# proiect_schematic_v19.net
KiCad netlist of a schematic drawn in EAGLE
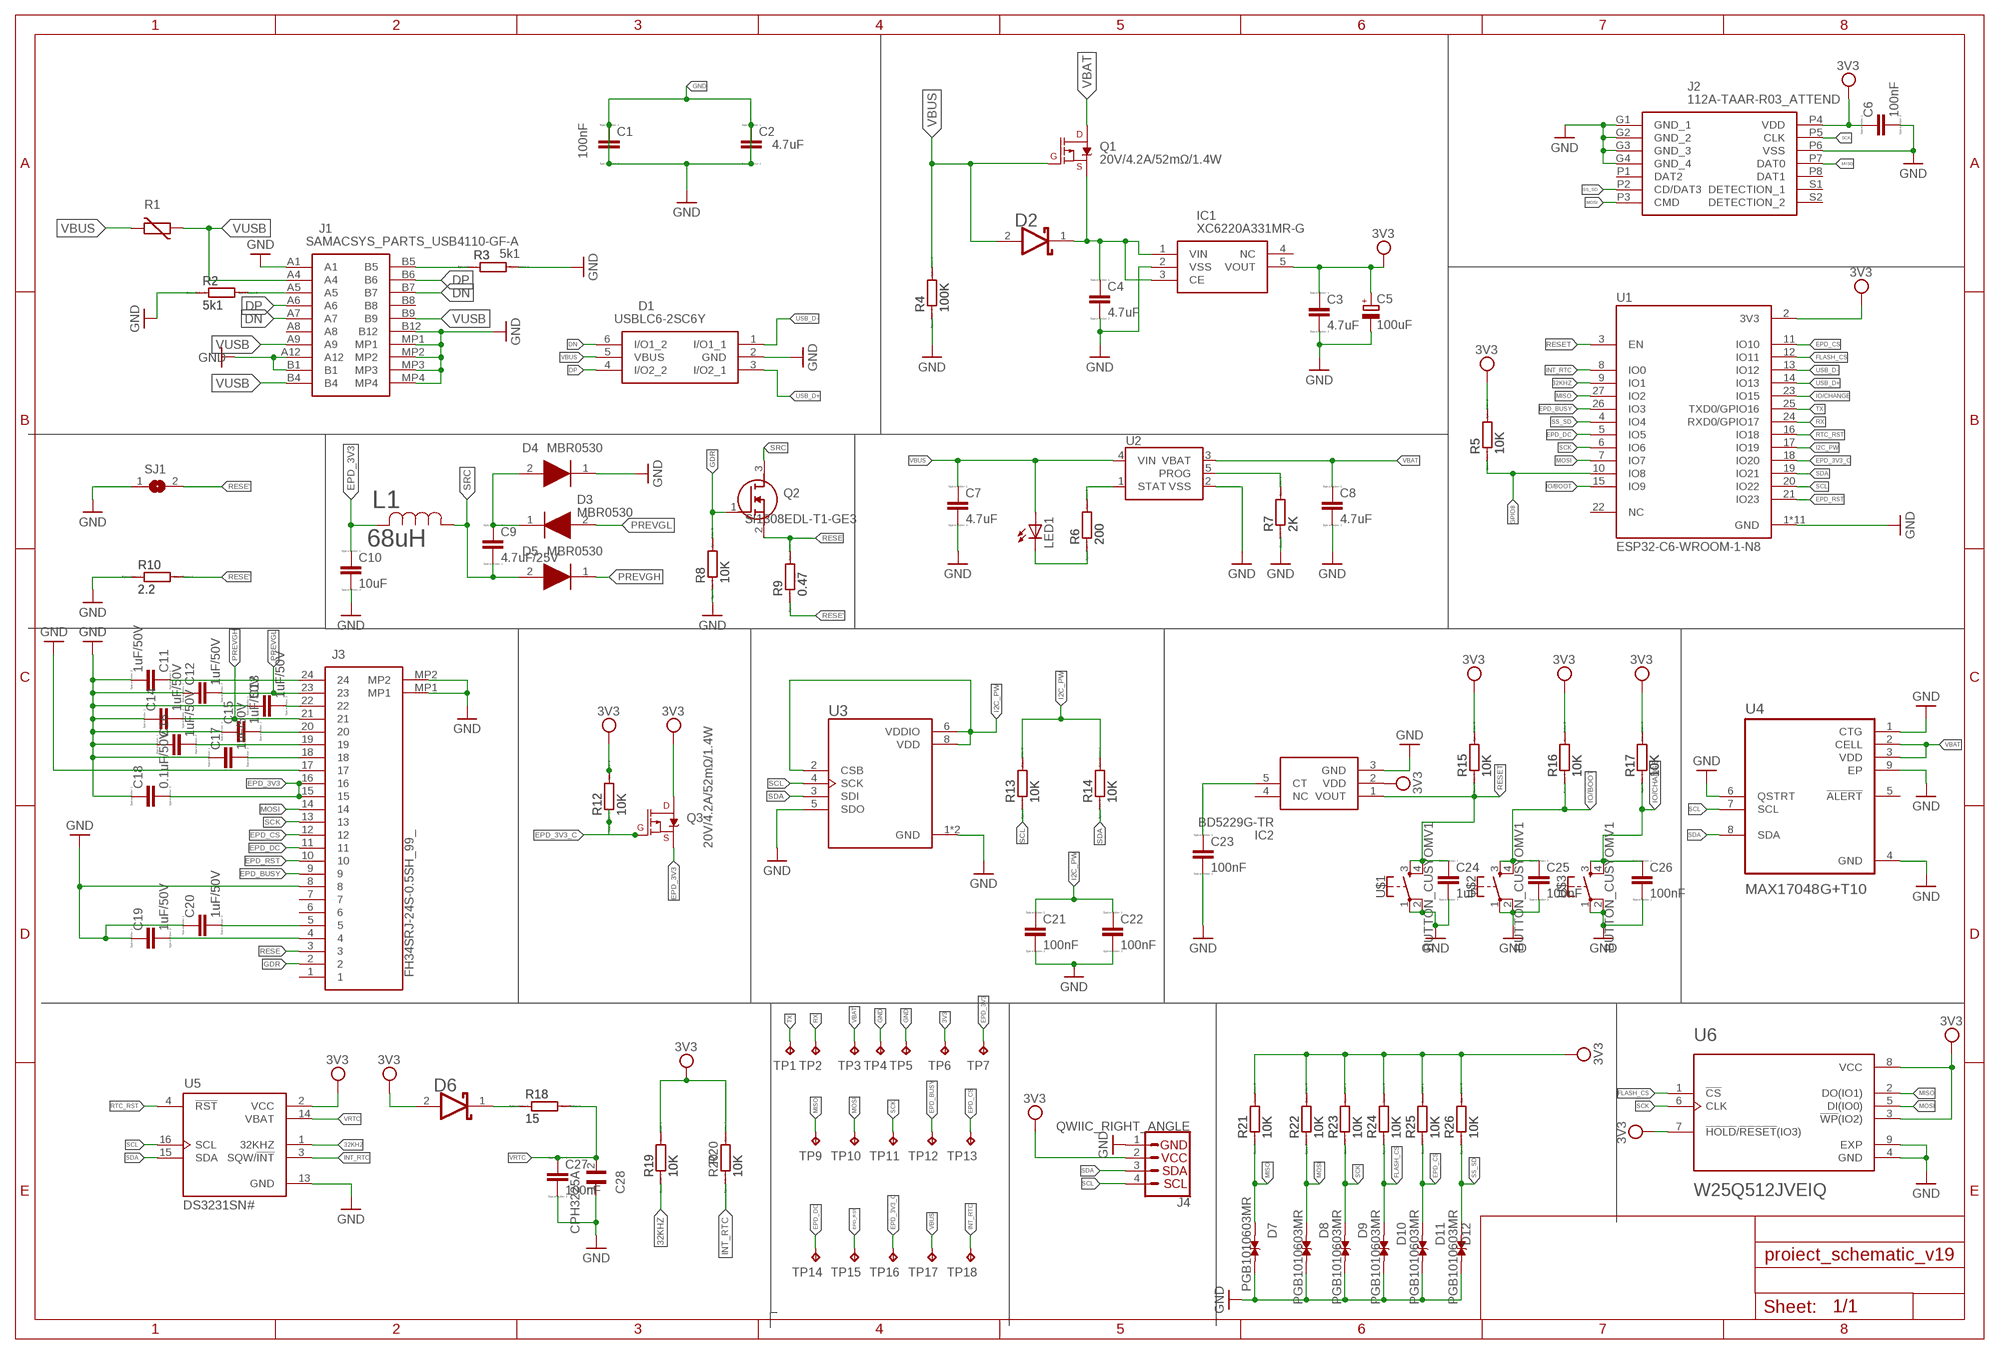
[diagram p0: schematic, sheet 1]

(export (version "E")
  (design (tool "Eeschema 10.0.6"))
  (components
    (comp (ref "C1")
      (value "100nF")
      (footprint "eagle-import:ESP32_WROVER_EAGLE-LTSPICE_C0402")
      (libsource (lib "eagle-import") (part "ESP32_WROVER_EAGLE-LTSPICE_CC0402"))
    )
    (comp (ref "C2")
      (value "4.7uF")
      (footprint "eagle-import:ESP32_WROVER_EAGLE-LTSPICE_C0402")
      (libsource (lib "eagle-import") (part "ESP32_WROVER_EAGLE-LTSPICE_CC0402"))
    )
    (comp (ref "C3")
      (value "4.7uF")
      (footprint "eagle-import:EAGLE-LTSPICE_C0402")
      (libsource (lib "eagle-import") (part "EAGLE-LTSPICE_CC0402"))
    )
    (comp (ref "C4")
      (value "4.7uF")
      (footprint "eagle-import:EAGLE-LTSPICE_C0402")
      (libsource (lib "eagle-import") (part "EAGLE-LTSPICE_CC0402"))
    )
    (comp (ref "C5")
      (value "100uF")
      (footprint "eagle-import:RCL_CT3528")
      (libsource (lib "eagle-import") (part "RCL_CPOL-EUCT3528"))
    )
    (comp (ref "C6")
      (value "100nF")
      (footprint "eagle-import:ESP32_WROVER_EAGLE-LTSPICE_C0402")
      (libsource (lib "eagle-import") (part "ESP32_WROVER_EAGLE-LTSPICE_CC0402"))
    )
    (comp (ref "C7")
      (value "4.7uF")
      (footprint "eagle-import:ESP32_WROVER_EAGLE-LTSPICE_C0402")
      (libsource (lib "eagle-import") (part "ESP32_WROVER_EAGLE-LTSPICE_CC0402"))
    )
    (comp (ref "C8")
      (value "4.7uF")
      (footprint "eagle-import:ESP32_WROVER_EAGLE-LTSPICE_C0402")
      (libsource (lib "eagle-import") (part "ESP32_WROVER_EAGLE-LTSPICE_CC0402"))
    )
    (comp (ref "C9")
      (value "4.7uF/25V")
      (footprint "eagle-import:ESP32_WROVER_EAGLE-LTSPICE_C0402")
      (libsource (lib "eagle-import") (part "ESP32_WROVER_EAGLE-LTSPICE_CC0402"))
    )
    (comp (ref "C10")
      (value "10uF")
      (footprint "eagle-import:ESP32_WROVER_EAGLE-LTSPICE_C0402")
      (libsource (lib "eagle-import") (part "ESP32_WROVER_EAGLE-LTSPICE_CC0402"))
    )
    (comp (ref "C11")
      (value "1uF/50V")
      (footprint "eagle-import:ESP32_WROVER_EAGLE-LTSPICE_C0402")
      (libsource (lib "eagle-import") (part "ESP32_WROVER_EAGLE-LTSPICE_CC0402"))
    )
    (comp (ref "C12")
      (value "1uF/50V")
      (footprint "eagle-import:ESP32_WROVER_EAGLE-LTSPICE_C0402")
      (libsource (lib "eagle-import") (part "ESP32_WROVER_EAGLE-LTSPICE_CC0402"))
    )
    (comp (ref "C13")
      (value "1uF/50V")
      (footprint "eagle-import:ESP32_WROVER_EAGLE-LTSPICE_C0402")
      (libsource (lib "eagle-import") (part "ESP32_WROVER_EAGLE-LTSPICE_CC0402"))
    )
    (comp (ref "C14")
      (value "1uF/50V")
      (footprint "eagle-import:ESP32_WROVER_EAGLE-LTSPICE_C0402")
      (libsource (lib "eagle-import") (part "ESP32_WROVER_EAGLE-LTSPICE_CC0402"))
    )
    (comp (ref "C15")
      (value "1uF/50V")
      (footprint "eagle-import:ESP32_WROVER_EAGLE-LTSPICE_C0402")
      (libsource (lib "eagle-import") (part "ESP32_WROVER_EAGLE-LTSPICE_CC0402"))
    )
    (comp (ref "C16")
      (value "1uF/50V")
      (footprint "eagle-import:ESP32_WROVER_EAGLE-LTSPICE_C0402")
      (libsource (lib "eagle-import") (part "ESP32_WROVER_EAGLE-LTSPICE_CC0402"))
    )
    (comp (ref "C17")
      (value "1uF/50V")
      (footprint "eagle-import:ESP32_WROVER_EAGLE-LTSPICE_C0402")
      (libsource (lib "eagle-import") (part "ESP32_WROVER_EAGLE-LTSPICE_CC0402"))
    )
    (comp (ref "C18")
      (value "0.1uF/50V")
      (footprint "eagle-import:ESP32_WROVER_EAGLE-LTSPICE_C0402")
      (libsource (lib "eagle-import") (part "ESP32_WROVER_EAGLE-LTSPICE_CC0402"))
    )
    (comp (ref "C19")
      (value "1uF/50V")
      (footprint "eagle-import:ESP32_WROVER_EAGLE-LTSPICE_C0402")
      (libsource (lib "eagle-import") (part "ESP32_WROVER_EAGLE-LTSPICE_CC0402"))
    )
    (comp (ref "C20")
      (value "1uF/50V")
      (footprint "eagle-import:ESP32_WROVER_EAGLE-LTSPICE_C0402")
      (libsource (lib "eagle-import") (part "ESP32_WROVER_EAGLE-LTSPICE_CC0402"))
    )
    (comp (ref "C21")
      (value "100nF")
      (footprint "eagle-import:ESP32_WROVER_EAGLE-LTSPICE_C0402")
      (libsource (lib "eagle-import") (part "ESP32_WROVER_EAGLE-LTSPICE_CC0402"))
    )
    (comp (ref "C22")
      (value "100nF")
      (footprint "eagle-import:ESP32_WROVER_EAGLE-LTSPICE_C0402")
      (libsource (lib "eagle-import") (part "ESP32_WROVER_EAGLE-LTSPICE_CC0402"))
    )
    (comp (ref "C23")
      (value "100nF")
      (footprint "eagle-import:ESP32_WROVER_EAGLE-LTSPICE_C0402")
      (libsource (lib "eagle-import") (part "ESP32_WROVER_EAGLE-LTSPICE_CC0402"))
    )
    (comp (ref "C24")
      (value "1uF")
      (footprint "eagle-import:ESP32_WROVER_EAGLE-LTSPICE_C0402")
      (libsource (lib "eagle-import") (part "ESP32_WROVER_EAGLE-LTSPICE_CC0402"))
    )
    (comp (ref "C25")
      (value "100nF")
      (footprint "eagle-import:ESP32_WROVER_EAGLE-LTSPICE_C0402")
      (libsource (lib "eagle-import") (part "ESP32_WROVER_EAGLE-LTSPICE_CC0402"))
    )
    (comp (ref "C26")
      (value "100nF")
      (footprint "eagle-import:ESP32_WROVER_EAGLE-LTSPICE_C0402")
      (libsource (lib "eagle-import") (part "ESP32_WROVER_EAGLE-LTSPICE_CC0402"))
    )
    (comp (ref "C27")
      (value "100nF")
      (footprint "eagle-import:ESP32_WROVER_EAGLE-LTSPICE_C0402")
      (libsource (lib "eagle-import") (part "ESP32_WROVER_EAGLE-LTSPICE_CC0402"))
    )
    (comp (ref "C28")
      (value "CPH3225A")
      (footprint "eagle-import:CAPCP3225X100N")
      (fields (field (name "MF") "Seiko Instruments"))
      (libsource (lib "eagle-import") (part "CPH3225A"))
    )
    (comp (ref "D1")
      (value "USBLC6-2SC6Y")
      (footprint "eagle-import:SOT95P280X145-6N")
      (fields (field (name "MF") "STMicroelectronics"))
      (libsource (lib "eagle-import") (part "USBLC6-2SC6Y"))
    )
    (comp (ref "D2")
      (value "ESP32_WROVER_AVX---SD0805S020S1R0_AVX_SD0805S020S1R0_0_0AVX_SD0805S020S1R0_0_0")
      (footprint "eagle-import:ESP32_WROVER_AVX---SD0805S020S1R0_AVX_SD0805S020S1R0_0")
      (fields
        (field (name "DIGIKEY_PART_NUMBER") "478-7800-1-ND")
        (field (name "MF") "AVX")
        (field (name "MOUSER_PART_NUMBER") "581-SD0805S020S1R0")
      )
      (libsource (lib "eagle-import") (part "ESP32_WROVER_AVX---SD0805S020S1R0_AVX_SD0805S020S1R0_0_0AVX_SD0805S020S1R0_0_0"))
    )
    (comp (ref "D3")
      (value "MBR0530")
      (footprint "eagle-import:SOD3716X135N")
      (fields (field (name "MF") "ON Semiconductor"))
      (libsource (lib "eagle-import") (part "MBR0530"))
    )
    (comp (ref "D4")
      (value "MBR0530")
      (footprint "eagle-import:SOD3716X135N")
      (fields (field (name "MF") "ON Semiconductor"))
      (libsource (lib "eagle-import") (part "MBR0530"))
    )
    (comp (ref "D5")
      (value "MBR0530")
      (footprint "eagle-import:SOD3716X135N")
      (fields (field (name "MF") "ON Semiconductor"))
      (libsource (lib "eagle-import") (part "MBR0530"))
    )
    (comp (ref "D6")
      (value "ESP32_WROVER_AVX---SD0805S020S1R0_AVX_SD0805S020S1R0_0_0AVX_SD0805S020S1R0_0_0")
      (footprint "eagle-import:ESP32_WROVER_AVX---SD0805S020S1R0_AVX_SD0805S020S1R0_0")
      (fields
        (field (name "DIGIKEY_PART_NUMBER") "478-7800-1-ND")
        (field (name "MF") "AVX")
        (field (name "MOUSER_PART_NUMBER") "581-SD0805S020S1R0")
      )
      (libsource (lib "eagle-import") (part "ESP32_WROVER_AVX---SD0805S020S1R0_AVX_SD0805S020S1R0_0_0AVX_SD0805S020S1R0_0_0"))
    )
    (comp (ref "D7")
      (value "PGB1010603MR")
      (footprint "eagle-import:DIOC1608X36N")
      (fields (field (name "MF") "Littelfuse Inc."))
      (libsource (lib "eagle-import") (part "PGB1010603MR"))
    )
    (comp (ref "D8")
      (value "PGB1010603MR")
      (footprint "eagle-import:DIOC1608X36N")
      (fields (field (name "MF") "Littelfuse Inc."))
      (libsource (lib "eagle-import") (part "PGB1010603MR"))
    )
    (comp (ref "D9")
      (value "PGB1010603MR")
      (footprint "eagle-import:DIOC1608X36N")
      (fields (field (name "MF") "Littelfuse Inc."))
      (libsource (lib "eagle-import") (part "PGB1010603MR"))
    )
    (comp (ref "D10")
      (value "PGB1010603MR")
      (footprint "eagle-import:DIOC1608X36N")
      (fields (field (name "MF") "Littelfuse Inc."))
      (libsource (lib "eagle-import") (part "PGB1010603MR"))
    )
    (comp (ref "D11")
      (value "PGB1010603MR")
      (footprint "eagle-import:DIOC1608X36N")
      (fields (field (name "MF") "Littelfuse Inc."))
      (libsource (lib "eagle-import") (part "PGB1010603MR"))
    )
    (comp (ref "D12")
      (value "PGB1010603MR")
      (footprint "eagle-import:DIOC1608X36N")
      (fields (field (name "MF") "Littelfuse Inc."))
      (libsource (lib "eagle-import") (part "PGB1010603MR"))
    )
    (comp (ref "IC1")
      (value "XC6220A331MR-G")
      (footprint "eagle-import:SOT95P280X120-5N")
      (fields (field (name "MOUSER_PART_NUMBER") "865-XC6220A331MR-G"))
      (libsource (lib "eagle-import") (part "XC6220A331MR-G"))
    )
    (comp (ref "IC2")
      (value "BD5229G-TR")
      (footprint "eagle-import:SOT95P280X125-5N")
      (fields (field (name "MOUSER_PART_NUMBER") "755-BD5229G-TR"))
      (libsource (lib "eagle-import") (part "BD5229G-TR"))
    )
    (comp (ref "J1")
      (value "SAMACSYS_PARTS_USB4110-GF-A")
      (footprint "eagle-import:SAMACSYS_PARTS_USB4110GFA")
      (fields
        (field (name "MANUFACTURER_PART_NUMBER") "USB4110-GF-A")
        (field (name "MOUSER_PART_NUMBER") "640-USB4110-GF-A")
      )
      (libsource (lib "eagle-import") (part "SAMACSYS_PARTS_USB4110-GF-A"))
    )
    (comp (ref "J2")
      (value "112A-TAAR-R03_ATTEND")
      (footprint "eagle-import:112ATAARR03ATTEND")
      (fields (field (name "MANUFACTURER_PART_NUMBER") "112A-TAAR-R03 ATTEND"))
      (libsource (lib "eagle-import") (part "112A-TAAR-R03_ATTEND"))
    )
    (comp (ref "J3")
      (value "FH34SRJ-24S-0.5SH_99_")
      (footprint "eagle-import:FH34SRJ24S05SH99")
      (fields
        (field (name "MANUFACTURER_PART_NUMBER") "FH34SRJ-24S-0.5SH(99)")
        (field (name "MOUSER_PART_NUMBER") "798-FH34SRJ24S05SH99")
      )
      (libsource (lib "eagle-import") (part "FH34SRJ-24S-0.5SH_99_"))
    )
    (comp (ref "J4")
      (value "QWIIC_RIGHT_ANGLE")
      (footprint "eagle-import:JST04_1MM_RA")
      (libsource (lib "eagle-import") (part "QWIIC_CONNECTORJS-1MM"))
    )
    (comp (ref "L1")
      (value "68uH")
      (footprint "eagle-import:IND_4828-WE-TPC_WRE")
      (fields
        (field (name "MANUFACTURER_PART_NUMBER") "744043680")
        (field (name "COPYRIGHT") "Copyright (C) 2024 Ultra Librarian. All rights reserved.")
      )
      (libsource (lib "eagle-import") (part "744043680IND_4828-WE-TPC_WRE"))
    )
    (comp (ref "LED1")
      (value "ADAFRUIT_LEDCHIP-LED0603")
      (footprint "eagle-import:ADAFRUIT_CHIP-LED0603")
      (libsource (lib "eagle-import") (part "ADAFRUIT_LEDCHIP-LED0603"))
    )
    (comp (ref "Q1")
      (value "20V/4.2A/52mΩ/1.4W")
      (footprint "eagle-import:ESP32_WROVER_SPARKFUN-DISCRETESEMI_SOT23-3")
      (libsource (lib "eagle-import") (part "ESP32_WROVER_SPARKFUN-DISCRETESEMI_MOSFET_PCH-DMG2305UX-7"))
    )
    (comp (ref "Q2")
      (value "SI1308EDL-T1-GE3")
      (footprint "eagle-import:SOT65P210X110-3N")
      (fields (field (name "MF") "Vishay Siliconix"))
      (libsource (lib "eagle-import") (part "SI1308EDL-T1-GE3"))
    )
    (comp (ref "Q3")
      (value "20V/4.2A/52mΩ/1.4W")
      (footprint "eagle-import:ESP32_WROVER_SPARKFUN-DISCRETESEMI_SOT23-3")
      (libsource (lib "eagle-import") (part "ESP32_WROVER_SPARKFUN-DISCRETESEMI_MOSFET_PCH-DMG2305UX-7"))
    )
    (comp (ref "R1")
      (value "ESP32C6_VARISTORCN1812")
      (footprint "eagle-import:ESP32C6_VARISTOR_CT_CN1812")
      (libsource (lib "eagle-import") (part "ESP32C6_VARISTORCN1812"))
    )
    (comp (ref "R2")
      (value "5k1")
      (footprint "eagle-import:ESP32_WROVER_EAGLE-LTSPICE_R0402")
      (libsource (lib "eagle-import") (part "ESP32_WROVER_EAGLE-LTSPICE_RR0402"))
    )
    (comp (ref "R3")
      (value "5k1")
      (footprint "eagle-import:ESP32_WROVER_EAGLE-LTSPICE_R0402")
      (libsource (lib "eagle-import") (part "ESP32_WROVER_EAGLE-LTSPICE_RR0402"))
    )
    (comp (ref "R4")
      (value "100K")
      (footprint "eagle-import:ESP32_WROVER_EAGLE-LTSPICE_R0402")
      (libsource (lib "eagle-import") (part "ESP32_WROVER_EAGLE-LTSPICE_RR0402"))
    )
    (comp (ref "R5")
      (value "10K")
      (footprint "eagle-import:ESP32_WROVER_EAGLE-LTSPICE_R0402")
      (libsource (lib "eagle-import") (part "ESP32_WROVER_EAGLE-LTSPICE_RR0402"))
    )
    (comp (ref "R6")
      (value "200")
      (footprint "eagle-import:ESP32_WROVER_EAGLE-LTSPICE_R0402")
      (libsource (lib "eagle-import") (part "ESP32_WROVER_EAGLE-LTSPICE_RR0402"))
    )
    (comp (ref "R7")
      (value "2K")
      (footprint "eagle-import:ESP32_WROVER_EAGLE-LTSPICE_R0402")
      (libsource (lib "eagle-import") (part "ESP32_WROVER_EAGLE-LTSPICE_RR0402"))
    )
    (comp (ref "R8")
      (value "10K")
      (footprint "eagle-import:ESP32_WROVER_EAGLE-LTSPICE_R0402")
      (libsource (lib "eagle-import") (part "ESP32_WROVER_EAGLE-LTSPICE_RR0402"))
    )
    (comp (ref "R9")
      (value "0.47")
      (footprint "eagle-import:ESP32_WROVER_EAGLE-LTSPICE_R0402")
      (libsource (lib "eagle-import") (part "ESP32_WROVER_EAGLE-LTSPICE_RR0402"))
    )
    (comp (ref "R10")
      (value "2.2")
      (footprint "eagle-import:ESP32_WROVER_EAGLE-LTSPICE_R0402")
      (libsource (lib "eagle-import") (part "ESP32_WROVER_EAGLE-LTSPICE_RR0402"))
    )
    (comp (ref "R12")
      (value "10K")
      (footprint "eagle-import:ESP32_WROVER_EAGLE-LTSPICE_R0402")
      (libsource (lib "eagle-import") (part "ESP32_WROVER_EAGLE-LTSPICE_RR0402"))
    )
    (comp (ref "R13")
      (value "10K")
      (footprint "eagle-import:ESP32_WROVER_EAGLE-LTSPICE_R0402")
      (libsource (lib "eagle-import") (part "ESP32_WROVER_EAGLE-LTSPICE_RR0402"))
    )
    (comp (ref "R14")
      (value "10K")
      (footprint "eagle-import:ESP32_WROVER_EAGLE-LTSPICE_R0402")
      (libsource (lib "eagle-import") (part "ESP32_WROVER_EAGLE-LTSPICE_RR0402"))
    )
    (comp (ref "R15")
      (value "10K")
      (footprint "eagle-import:ESP32_WROVER_EAGLE-LTSPICE_R0402")
      (libsource (lib "eagle-import") (part "ESP32_WROVER_EAGLE-LTSPICE_RR0402"))
    )
    (comp (ref "R16")
      (value "10K")
      (footprint "eagle-import:ESP32_WROVER_EAGLE-LTSPICE_R0402")
      (libsource (lib "eagle-import") (part "ESP32_WROVER_EAGLE-LTSPICE_RR0402"))
    )
    (comp (ref "R17")
      (value "10K")
      (footprint "eagle-import:ESP32_WROVER_EAGLE-LTSPICE_R0402")
      (libsource (lib "eagle-import") (part "ESP32_WROVER_EAGLE-LTSPICE_RR0402"))
    )
    (comp (ref "R18")
      (value "15")
      (footprint "eagle-import:ESP32_WROVER_EAGLE-LTSPICE_R0402")
      (libsource (lib "eagle-import") (part "ESP32_WROVER_EAGLE-LTSPICE_RR0402"))
    )
    (comp (ref "R19")
      (value "10K")
      (footprint "eagle-import:ESP32_WROVER_EAGLE-LTSPICE_R0402")
      (libsource (lib "eagle-import") (part "ESP32_WROVER_EAGLE-LTSPICE_RR0402"))
    )
    (comp (ref "R20")
      (value "10K")
      (footprint "eagle-import:ESP32_WROVER_EAGLE-LTSPICE_R0402")
      (libsource (lib "eagle-import") (part "ESP32_WROVER_EAGLE-LTSPICE_RR0402"))
    )
    (comp (ref "R21")
      (value "10K")
      (footprint "eagle-import:ESP32_WROVER_EAGLE-LTSPICE_R0402")
      (libsource (lib "eagle-import") (part "ESP32_WROVER_EAGLE-LTSPICE_RR0402"))
    )
    (comp (ref "R22")
      (value "10K")
      (footprint "eagle-import:ESP32_WROVER_EAGLE-LTSPICE_R0402")
      (libsource (lib "eagle-import") (part "ESP32_WROVER_EAGLE-LTSPICE_RR0402"))
    )
    (comp (ref "R23")
      (value "10K")
      (footprint "eagle-import:ESP32_WROVER_EAGLE-LTSPICE_R0402")
      (libsource (lib "eagle-import") (part "ESP32_WROVER_EAGLE-LTSPICE_RR0402"))
    )
    (comp (ref "R24")
      (value "10K")
      (footprint "eagle-import:ESP32_WROVER_EAGLE-LTSPICE_R0402")
      (libsource (lib "eagle-import") (part "ESP32_WROVER_EAGLE-LTSPICE_RR0402"))
    )
    (comp (ref "R25")
      (value "10K")
      (footprint "eagle-import:ESP32_WROVER_EAGLE-LTSPICE_R0402")
      (libsource (lib "eagle-import") (part "ESP32_WROVER_EAGLE-LTSPICE_RR0402"))
    )
    (comp (ref "R26")
      (value "10K")
      (footprint "eagle-import:ESP32_WROVER_EAGLE-LTSPICE_R0402")
      (libsource (lib "eagle-import") (part "ESP32_WROVER_EAGLE-LTSPICE_RR0402"))
    )
    (comp (ref "SJ1") (value "SJ") (footprint "eagle-import:SJ") (libsource (lib "eagle-import") (part "SJ")))
    (comp (ref "TP1")
      (value "TPTP20R")
      (footprint "eagle-import:TP20R")
      (libsource (lib "eagle-import") (part "TPTP20R"))
    )
    (comp (ref "TP2")
      (value "TPTP20R")
      (footprint "eagle-import:TP20R")
      (libsource (lib "eagle-import") (part "TPTP20R"))
    )
    (comp (ref "TP3")
      (value "TPTP20R")
      (footprint "eagle-import:TP20R")
      (libsource (lib "eagle-import") (part "TPTP20R"))
    )
    (comp (ref "TP4")
      (value "TPTP20R")
      (footprint "eagle-import:TP20R")
      (libsource (lib "eagle-import") (part "TPTP20R"))
    )
    (comp (ref "TP5")
      (value "TPTP20R")
      (footprint "eagle-import:TP20R")
      (libsource (lib "eagle-import") (part "TPTP20R"))
    )
    (comp (ref "TP6")
      (value "TPTP20R")
      (footprint "eagle-import:TP20R")
      (libsource (lib "eagle-import") (part "TPTP20R"))
    )
    (comp (ref "TP7")
      (value "TPTP20R")
      (footprint "eagle-import:TP20R")
      (libsource (lib "eagle-import") (part "TPTP20R"))
    )
    (comp (ref "TP9")
      (value "TPTP20R")
      (footprint "eagle-import:TP20R")
      (libsource (lib "eagle-import") (part "TPTP20R"))
    )
    (comp (ref "TP10")
      (value "TPTP20R")
      (footprint "eagle-import:TP20R")
      (libsource (lib "eagle-import") (part "TPTP20R"))
    )
    (comp (ref "TP11")
      (value "TPTP20R")
      (footprint "eagle-import:TP20R")
      (libsource (lib "eagle-import") (part "TPTP20R"))
    )
    (comp (ref "TP12")
      (value "TPTP20R")
      (footprint "eagle-import:TP20R")
      (libsource (lib "eagle-import") (part "TPTP20R"))
    )
    (comp (ref "TP13")
      (value "TPTP20R")
      (footprint "eagle-import:TP20R")
      (libsource (lib "eagle-import") (part "TPTP20R"))
    )
    (comp (ref "TP14")
      (value "TPTP20R")
      (footprint "eagle-import:TP20R")
      (libsource (lib "eagle-import") (part "TPTP20R"))
    )
    (comp (ref "TP15")
      (value "TPTP20R")
      (footprint "eagle-import:TP20R")
      (libsource (lib "eagle-import") (part "TPTP20R"))
    )
    (comp (ref "TP16")
      (value "TPTP20R")
      (footprint "eagle-import:TP20R")
      (libsource (lib "eagle-import") (part "TPTP20R"))
    )
    (comp (ref "TP17")
      (value "TPTP20R")
      (footprint "eagle-import:TP20R")
      (libsource (lib "eagle-import") (part "TPTP20R"))
    )
    (comp (ref "TP18")
      (value "TPTP20R")
      (footprint "eagle-import:TP20R")
      (libsource (lib "eagle-import") (part "TPTP20R"))
    )
    (comp (ref "U$1")
      (value "BUTTON_CUSYOMV1")
      (footprint "eagle-import:MYBUTTON")
      (libsource (lib "eagle-import") (part "BUTTON_CUSYOMV1"))
    )
    (comp (ref "U$2")
      (value "BUTTON_CUSYOMV1")
      (footprint "eagle-import:MYBUTTON")
      (libsource (lib "eagle-import") (part "BUTTON_CUSYOMV1"))
    )
    (comp (ref "U$3")
      (value "BUTTON_CUSYOMV1")
      (footprint "eagle-import:MYBUTTON")
      (libsource (lib "eagle-import") (part "BUTTON_CUSYOMV1"))
    )
    (comp (ref "U1")
      (value "ESP32-C6-WROOM-1-N8")
      (footprint "eagle-import:XCVR_ESP32-C6-WROOM-1-N8")
      (fields (field (name "MF") "Espressif Systems"))
      (libsource (lib "eagle-import") (part "ESP32-C6-WROOM-1-N8"))
    )
    (comp (ref "U2")
      (value "ESP32_WROVER_SPARKFUN-IC-POWER_MCP73831")
      (footprint "eagle-import:ESP32_WROVER_SPARKFUN-IC-POWER_SOT23-5")
      (libsource (lib "eagle-import") (part "ESP32_WROVER_SPARKFUN-IC-POWER_MCP73831"))
    )
    (comp (ref "U3")
      (value "ESP32_WROVER_BME680_BME680")
      (footprint "eagle-import:ESP32_WROVER_BME680_PSON80P300X300X100-8N")
      (fields (field (name "MF") "Bosch Sensortec") (field (name "MP") "BME680"))
      (libsource (lib "eagle-import") (part "ESP32_WROVER_BME680_BME680"))
    )
    (comp (ref "U4")
      (value "MAX17048G+T10")
      (footprint "eagle-import:SON50P200X200X80-9N")
      (fields (field (name "MF") "Analog Devices"))
      (libsource (lib "eagle-import") (part "MAX17048G+T10"))
    )
    (comp (ref "U5")
      (value "DS3231SN#")
      (footprint "eagle-import:SOIC127P1032X265-16N")
      (fields (field (name "MF") "Analog Devices"))
      (libsource (lib "eagle-import") (part "DS3231SN#"))
    )
    (comp (ref "U6")
      (value "W25Q512JVEIQ")
      (footprint "eagle-import:SON127P600X800X80-9N")
      (fields (field (name "MF") "Winbond Electronics"))
      (libsource (lib "eagle-import") (part "W25Q512JVEIQ"))
    )
  )
  (nets
    (net (code "1") (name "3V3") (class "Default")
      (node (ref "C3") (pin "1") (pinfunction "1_1") (pintype "passive"))
      (node (ref "C5") (pin "+") (pinfunction "+_+") (pintype "passive"))
      (node (ref "C6") (pin "1") (pinfunction "1_1") (pintype "passive"))
      (node (ref "D6") (pin "2") (pinfunction "ANODE_2") (pintype "bidirectional"))
      (node (ref "IC1") (pin "5") (pinfunction "VOUT_5") (pintype "bidirectional"))
      (node (ref "IC2") (pin "2") (pinfunction "VDD_2") (pintype "bidirectional"))
      (node (ref "J2") (pin "P4") (pinfunction "VDD_P4") (pintype "bidirectional"))
      (node (ref "J4") (pin "2") (pinfunction "2_2") (pintype "power_in"))
      (node (ref "Q3") (pin "3") (pinfunction "D_3") (pintype "bidirectional"))
      (node (ref "R12") (pin "2") (pinfunction "2_2") (pintype "passive"))
      (node (ref "R15") (pin "2") (pinfunction "2_2") (pintype "passive"))
      (node (ref "R16") (pin "2") (pinfunction "2_2") (pintype "passive"))
      (node (ref "R17") (pin "2") (pinfunction "2_2") (pintype "passive"))
      (node (ref "R19") (pin "2") (pinfunction "2_2") (pintype "passive"))
      (node (ref "R20") (pin "2") (pinfunction "2_2") (pintype "passive"))
      (node (ref "R21") (pin "2") (pinfunction "2_2") (pintype "passive"))
      (node (ref "R22") (pin "2") (pinfunction "2_2") (pintype "passive"))
      (node (ref "R23") (pin "2") (pinfunction "2_2") (pintype "passive"))
      (node (ref "R24") (pin "2") (pinfunction "2_2") (pintype "passive"))
      (node (ref "R25") (pin "2") (pinfunction "2_2") (pintype "passive"))
      (node (ref "R26") (pin "2") (pinfunction "2_2") (pintype "passive"))
      (node (ref "R5") (pin "2") (pinfunction "2_2") (pintype "passive"))
      (node (ref "TP6") (pin "TP") (pinfunction "TP_TP") (pintype "input"))
      (node (ref "U1") (pin "2") (pinfunction "3V3_2") (pintype "power_in"))
      (node (ref "U5") (pin "2") (pinfunction "VCC_2") (pintype "power_in"))
      (node (ref "U6") (pin "3") (pinfunction "~{WP}(IO2)_3") (pintype "bidirectional"))
      (node (ref "U6") (pin "7") (pinfunction "~{HOLD}/~{RESET}(IO3)_7") (pintype "bidirectional"))
      (node (ref "U6") (pin "8") (pinfunction "VCC_8") (pintype "power_in"))
    )
    (net (code "2") (name "32KHZ") (class "Default")
      (node (ref "R19") (pin "1") (pinfunction "1_1") (pintype "passive"))
      (node (ref "U1") (pin "9") (pinfunction "IO1_9") (pintype "bidirectional"))
      (node (ref "U5") (pin "1") (pinfunction "32KHZ_1") (pintype "output"))
    )
    (net (code "3") (name "DN") (class "Default")
      (node (ref "D1") (pin "6") (pinfunction "I/O1_2_6") (pintype "bidirectional"))
      (node (ref "J1") (pin "A7") (pinfunction "A7_A7") (pintype "bidirectional"))
      (node (ref "J1") (pin "B7") (pinfunction "B7_B7") (pintype "bidirectional"))
    )
    (net (code "4") (name "DP") (class "Default")
      (node (ref "D1") (pin "4") (pinfunction "I/O2_2_4") (pintype "bidirectional"))
      (node (ref "J1") (pin "A6") (pinfunction "A6_A6") (pintype "bidirectional"))
      (node (ref "J1") (pin "B6") (pinfunction "B6_B6") (pintype "bidirectional"))
    )
    (net (code "5") (name "EPD_3V3") (class "Default")
      (node (ref "C10") (pin "1") (pinfunction "1_1") (pintype "passive"))
      (node (ref "C18") (pin "2") (pinfunction "2_2") (pintype "passive"))
      (node (ref "J3") (pin "15") (pinfunction "15_15") (pintype "bidirectional"))
      (node (ref "J3") (pin "16") (pinfunction "16_16") (pintype "bidirectional"))
      (node (ref "L1") (pin "2") (pinfunction "2_2") (pintype "passive"))
      (node (ref "Q3") (pin "2") (pinfunction "S_2") (pintype "bidirectional"))
      (node (ref "TP7") (pin "TP") (pinfunction "TP_TP") (pintype "input"))
    )
    (net (code "6") (name "EPD_3V3_C") (class "Default")
      (node (ref "Q3") (pin "1") (pinfunction "G_1") (pintype "bidirectional"))
      (node (ref "R12") (pin "1") (pinfunction "1_1") (pintype "passive"))
      (node (ref "TP16") (pin "TP") (pinfunction "TP_TP") (pintype "input"))
      (node (ref "U1") (pin "18") (pinfunction "IO20_18") (pintype "bidirectional"))
    )
    (net (code "7") (name "EPD_BUSY") (class "Default")
      (node (ref "J3") (pin "9") (pinfunction "9_9") (pintype "bidirectional"))
      (node (ref "TP12") (pin "TP") (pinfunction "TP_TP") (pintype "input"))
      (node (ref "U1") (pin "26") (pinfunction "IO3_26") (pintype "bidirectional"))
    )
    (net (code "8") (name "EPD_CS") (class "Default")
      (node (ref "D11") (pin "1") (pinfunction "1_1") (pintype "passive"))
      (node (ref "J3") (pin "12") (pinfunction "12_12") (pintype "bidirectional"))
      (node (ref "R25") (pin "1") (pinfunction "1_1") (pintype "passive"))
      (node (ref "TP13") (pin "TP") (pinfunction "TP_TP") (pintype "input"))
      (node (ref "U1") (pin "11") (pinfunction "IO10_11") (pintype "bidirectional"))
    )
    (net (code "9") (name "EPD_DC") (class "Default")
      (node (ref "J3") (pin "11") (pinfunction "11_11") (pintype "bidirectional"))
      (node (ref "TP14") (pin "TP") (pinfunction "TP_TP") (pintype "input"))
      (node (ref "U1") (pin "5") (pinfunction "IO5_5") (pintype "bidirectional"))
    )
    (net (code "10") (name "EPD_RST") (class "Default")
      (node (ref "J3") (pin "10") (pinfunction "10_10") (pintype "bidirectional"))
      (node (ref "TP15") (pin "TP") (pinfunction "TP_TP") (pintype "input"))
      (node (ref "U1") (pin "21") (pinfunction "IO23_21") (pintype "bidirectional"))
    )
    (net (code "11") (name "FLASH_CS") (class "Default")
      (node (ref "D10") (pin "1") (pinfunction "1_1") (pintype "passive"))
      (node (ref "R24") (pin "1") (pinfunction "1_1") (pintype "passive"))
      (node (ref "U1") (pin "12") (pinfunction "IO11_12") (pintype "bidirectional"))
      (node (ref "U6") (pin "1") (pinfunction "~{CS}_1") (pintype "input"))
    )
    (net (code "12") (name "GDR") (class "Default")
      (node (ref "J3") (pin "2") (pinfunction "2_2") (pintype "bidirectional"))
      (node (ref "Q2") (pin "1") (pinfunction "G_1") (pintype "bidirectional"))
      (node (ref "R8") (pin "2") (pinfunction "2_2") (pintype "passive"))
    )
    (net (code "13") (name "GND") (class "Default")
      (node (ref "C1") (pin "1") (pinfunction "1_1") (pintype "passive"))
      (node (ref "C1") (pin "2") (pinfunction "2_2") (pintype "passive"))
      (node (ref "C10") (pin "2") (pinfunction "2_2") (pintype "passive"))
      (node (ref "C11") (pin "2") (pinfunction "2_2") (pintype "passive"))
      (node (ref "C12") (pin "1") (pinfunction "1_1") (pintype "passive"))
      (node (ref "C13") (pin "1") (pinfunction "1_1") (pintype "passive"))
      (node (ref "C14") (pin "1") (pinfunction "1_1") (pintype "passive"))
      (node (ref "C15") (pin "1") (pinfunction "1_1") (pintype "passive"))
      (node (ref "C16") (pin "1") (pinfunction "1_1") (pintype "passive"))
      (node (ref "C17") (pin "1") (pinfunction "1_1") (pintype "passive"))
      (node (ref "C18") (pin "1") (pinfunction "1_1") (pintype "passive"))
      (node (ref "C19") (pin "1") (pinfunction "1_1") (pintype "passive"))
      (node (ref "C2") (pin "1") (pinfunction "1_1") (pintype "passive"))
      (node (ref "C2") (pin "2") (pinfunction "2_2") (pintype "passive"))
      (node (ref "C20") (pin "1") (pinfunction "1_1") (pintype "passive"))
      (node (ref "C21") (pin "2") (pinfunction "2_2") (pintype "passive"))
      (node (ref "C22") (pin "2") (pinfunction "2_2") (pintype "passive"))
      (node (ref "C23") (pin "2") (pinfunction "2_2") (pintype "passive"))
      (node (ref "C24") (pin "2") (pinfunction "2_2") (pintype "passive"))
      (node (ref "C25") (pin "2") (pinfunction "2_2") (pintype "passive"))
      (node (ref "C26") (pin "2") (pinfunction "2_2") (pintype "passive"))
      (node (ref "C27") (pin "2") (pinfunction "2_2") (pintype "passive"))
      (node (ref "C28") (pin "1") (pinfunction "1_1") (pintype "passive"))
      (node (ref "C3") (pin "2") (pinfunction "2_2") (pintype "passive"))
      (node (ref "C4") (pin "2") (pinfunction "2_2") (pintype "passive"))
      (node (ref "C5") (pin "-") (pinfunction "-_-") (pintype "passive"))
      (node (ref "C6") (pin "2") (pinfunction "2_2") (pintype "passive"))
      (node (ref "C7") (pin "2") (pinfunction "2_2") (pintype "passive"))
      (node (ref "C8") (pin "2") (pinfunction "2_2") (pintype "passive"))
      (node (ref "D1") (pin "2") (pinfunction "GND_2") (pintype "bidirectional"))
      (node (ref "D10") (pin "2") (pinfunction "2_2") (pintype "passive"))
      (node (ref "D11") (pin "2") (pinfunction "2_2") (pintype "passive"))
      (node (ref "D12") (pin "2") (pinfunction "2_2") (pintype "passive"))
      (node (ref "D4") (pin "1") (pinfunction "K_1") (pintype "bidirectional"))
      (node (ref "D7") (pin "2") (pinfunction "2_2") (pintype "passive"))
      (node (ref "D8") (pin "2") (pinfunction "2_2") (pintype "passive"))
      (node (ref "D9") (pin "2") (pinfunction "2_2") (pintype "passive"))
      (node (ref "IC1") (pin "2") (pinfunction "VSS_2") (pintype "bidirectional"))
      (node (ref "IC2") (pin "3") (pinfunction "GND_3") (pintype "bidirectional"))
      (node (ref "J1") (pin "A1") (pinfunction "A1_A1") (pintype "bidirectional"))
      (node (ref "J1") (pin "A12") (pinfunction "A12_A12") (pintype "bidirectional"))
      (node (ref "J1") (pin "B1") (pinfunction "B1_B1") (pintype "bidirectional"))
      (node (ref "J1") (pin "B12") (pinfunction "B12_B12") (pintype "bidirectional"))
      (node (ref "J1") (pin "MP1") (pinfunction "MP1_MP1") (pintype "bidirectional"))
      (node (ref "J1") (pin "MP2") (pinfunction "MP2_MP2") (pintype "bidirectional"))
      (node (ref "J1") (pin "MP3") (pinfunction "MP3_MP3") (pintype "bidirectional"))
      (node (ref "J1") (pin "MP4") (pinfunction "MP4_MP4") (pintype "bidirectional"))
      (node (ref "J2") (pin "G1") (pinfunction "GND_1_G1") (pintype "bidirectional"))
      (node (ref "J2") (pin "G2") (pinfunction "GND_2_G2") (pintype "bidirectional"))
      (node (ref "J2") (pin "G3") (pinfunction "GND_3_G3") (pintype "bidirectional"))
      (node (ref "J2") (pin "G4") (pinfunction "GND_4_G4") (pintype "bidirectional"))
      (node (ref "J2") (pin "P6") (pinfunction "VSS_P6") (pintype "bidirectional"))
      (node (ref "J3") (pin "17") (pinfunction "17_17") (pintype "bidirectional"))
      (node (ref "J3") (pin "8") (pinfunction "8_8") (pintype "bidirectional"))
      (node (ref "J3") (pin "MP1") (pinfunction "MP1_MP1") (pintype "bidirectional"))
      (node (ref "J3") (pin "MP2") (pinfunction "MP2_MP2") (pintype "bidirectional"))
      (node (ref "J4") (pin "1") (pinfunction "1_1") (pintype "power_in"))
      (node (ref "R10") (pin "1") (pinfunction "1_1") (pintype "passive"))
      (node (ref "R2") (pin "1") (pinfunction "1_1") (pintype "passive"))
      (node (ref "R3") (pin "2") (pinfunction "2_2") (pintype "passive"))
      (node (ref "R4") (pin "1") (pinfunction "1_1") (pintype "passive"))
      (node (ref "R7") (pin "1") (pinfunction "1_1") (pintype "passive"))
      (node (ref "R8") (pin "1") (pinfunction "1_1") (pintype "passive"))
      (node (ref "SJ1") (pin "1") (pinfunction "1_1") (pintype "passive"))
      (node (ref "TP4") (pin "TP") (pinfunction "TP_TP") (pintype "input"))
      (node (ref "TP5") (pin "TP") (pinfunction "TP_TP") (pintype "input"))
      (node (ref "U$1") (pin "1") (pinfunction "1_1") (pintype "passive"))
      (node (ref "U$1") (pin "2") (pinfunction "2_2") (pintype "passive"))
      (node (ref "U$2") (pin "1") (pinfunction "1_1") (pintype "passive"))
      (node (ref "U$2") (pin "2") (pinfunction "2_2") (pintype "passive"))
      (node (ref "U$3") (pin "1") (pinfunction "1_1") (pintype "passive"))
      (node (ref "U$3") (pin "2") (pinfunction "2_2") (pintype "passive"))
      (node (ref "U1") (pin "1") (pinfunction "GND_1") (pintype "power_in"))
      (node (ref "U1") (pin "28") (pinfunction "GND_28") (pintype "power_in"))
      (node (ref "U1") (pin "29_1") (pinfunction "GND_29_1") (pintype "power_in"))
      (node (ref "U1") (pin "29_2") (pinfunction "GND_29_2") (pintype "power_in"))
      (node (ref "U1") (pin "29_3") (pinfunction "GND_29_3") (pintype "power_in"))
      (node (ref "U1") (pin "29_4") (pinfunction "GND_29_4") (pintype "power_in"))
      (node (ref "U1") (pin "29_5") (pinfunction "GND_29_5") (pintype "power_in"))
      (node (ref "U1") (pin "29_6") (pinfunction "GND_29_6") (pintype "power_in"))
      (node (ref "U1") (pin "29_7") (pinfunction "GND_29_7") (pintype "power_in"))
      (node (ref "U1") (pin "29_8") (pinfunction "GND_29_8") (pintype "power_in"))
      (node (ref "U1") (pin "29_9") (pinfunction "GND_29_9") (pintype "power_in"))
      (node (ref "U2") (pin "2") (pinfunction "VSS_2") (pintype "power_in"))
      (node (ref "U3") (pin "1") (pinfunction "GND_1") (pintype "power_in"))
      (node (ref "U3") (pin "5") (pinfunction "SDO_5") (pintype "bidirectional"))
      (node (ref "U3") (pin "7") (pinfunction "GND_7") (pintype "power_in"))
      (node (ref "U4") (pin "1") (pinfunction "CTG_1") (pintype "power_in"))
      (node (ref "U4") (pin "4") (pinfunction "GND_4") (pintype "power_in"))
      (node (ref "U4") (pin "6") (pinfunction "QSTRT_6") (pintype "input"))
      (node (ref "U4") (pin "9") (pinfunction "EP_9") (pintype "power_in"))
      (node (ref "U5") (pin "13") (pinfunction "GND_13") (pintype "power_in"))
      (node (ref "U6") (pin "4") (pinfunction "GND_4") (pintype "power_in"))
      (node (ref "U6") (pin "9") (pinfunction "EXP_9") (pintype "passive"))
    )
    (net (code "14") (name "GPIO8") (class "Default")
      (node (ref "R5") (pin "1") (pinfunction "1_1") (pintype "passive"))
      (node (ref "U1") (pin "10") (pinfunction "IO8_10") (pintype "bidirectional"))
    )
    (net (code "15") (name "I2C_PW") (class "Default")
      (node (ref "C21") (pin "1") (pinfunction "1_1") (pintype "passive"))
      (node (ref "C22") (pin "1") (pinfunction "1_1") (pintype "passive"))
      (node (ref "R13") (pin "2") (pinfunction "2_2") (pintype "passive"))
      (node (ref "R14") (pin "2") (pinfunction "2_2") (pintype "passive"))
      (node (ref "U1") (pin "17") (pinfunction "IO19_17") (pintype "bidirectional"))
      (node (ref "U3") (pin "2") (pinfunction "CSB_2") (pintype "input"))
      (node (ref "U3") (pin "6") (pinfunction "VDDIO_6") (pintype "power_in"))
      (node (ref "U3") (pin "8") (pinfunction "VDD_8") (pintype "power_in"))
    )
    (net (code "16") (name "INT_RTC") (class "Default")
      (node (ref "R20") (pin "1") (pinfunction "1_1") (pintype "passive"))
      (node (ref "TP18") (pin "TP") (pinfunction "TP_TP") (pintype "input"))
      (node (ref "U1") (pin "8") (pinfunction "IO0_8") (pintype "bidirectional"))
      (node (ref "U5") (pin "3") (pinfunction "SQW/~{INT}_3") (pintype "output"))
    )
    (net (code "17") (name "IO{slash}BOOT") (class "Default")
      (node (ref "C25") (pin "1") (pinfunction "1_1") (pintype "passive"))
      (node (ref "R16") (pin "1") (pinfunction "1_1") (pintype "passive"))
      (node (ref "U$2") (pin "3") (pinfunction "3_3") (pintype "passive"))
      (node (ref "U$2") (pin "4") (pinfunction "4_4") (pintype "passive"))
      (node (ref "U1") (pin "15") (pinfunction "IO9_15") (pintype "bidirectional"))
    )
    (net (code "18") (name "IO{slash}CHANGE") (class "Default")
      (node (ref "C26") (pin "1") (pinfunction "1_1") (pintype "passive"))
      (node (ref "R17") (pin "1") (pinfunction "1_1") (pintype "passive"))
      (node (ref "U$3") (pin "3") (pinfunction "3_3") (pintype "passive"))
      (node (ref "U$3") (pin "4") (pinfunction "4_4") (pintype "passive"))
      (node (ref "U1") (pin "23") (pinfunction "IO15_23") (pintype "bidirectional"))
    )
    (net (code "19") (name "MISO") (class "Default")
      (node (ref "D7") (pin "1") (pinfunction "1_1") (pintype "passive"))
      (node (ref "J2") (pin "P7") (pinfunction "DAT0_P7") (pintype "bidirectional"))
      (node (ref "R21") (pin "1") (pinfunction "1_1") (pintype "passive"))
      (node (ref "TP9") (pin "TP") (pinfunction "TP_TP") (pintype "input"))
      (node (ref "U1") (pin "27") (pinfunction "IO2_27") (pintype "bidirectional"))
      (node (ref "U6") (pin "2") (pinfunction "DO(IO1)_2") (pintype "bidirectional"))
    )
    (net (code "20") (name "MOSI") (class "Default")
      (node (ref "D8") (pin "1") (pinfunction "1_1") (pintype "passive"))
      (node (ref "J2") (pin "P3") (pinfunction "CMD_P3") (pintype "bidirectional"))
      (node (ref "J3") (pin "14") (pinfunction "14_14") (pintype "bidirectional"))
      (node (ref "R22") (pin "1") (pinfunction "1_1") (pintype "passive"))
      (node (ref "TP10") (pin "TP") (pinfunction "TP_TP") (pintype "input"))
      (node (ref "U1") (pin "7") (pinfunction "IO7_7") (pintype "bidirectional"))
      (node (ref "U6") (pin "5") (pinfunction "DI(IO0)_5") (pintype "bidirectional"))
    )
    (net (code "21") (name "Net-(C11-Pad1)") (class "Default")
      (node (ref "C11") (pin "1") (pinfunction "1_1") (pintype "passive"))
      (node (ref "J3") (pin "24") (pinfunction "24_24") (pintype "bidirectional"))
    )
    (net (code "22") (name "Net-(C13-Pad2)") (class "Default")
      (node (ref "C13") (pin "2") (pinfunction "2_2") (pintype "passive"))
      (node (ref "J3") (pin "22") (pinfunction "22_22") (pintype "bidirectional"))
    )
    (net (code "23") (name "Net-(C15-Pad2)") (class "Default")
      (node (ref "C15") (pin "2") (pinfunction "2_2") (pintype "passive"))
      (node (ref "J3") (pin "20") (pinfunction "20_20") (pintype "bidirectional"))
    )
    (net (code "24") (name "Net-(C16-Pad2)") (class "Default")
      (node (ref "C16") (pin "2") (pinfunction "2_2") (pintype "passive"))
      (node (ref "J3") (pin "19") (pinfunction "19_19") (pintype "bidirectional"))
    )
    (net (code "25") (name "Net-(C17-Pad2)") (class "Default")
      (node (ref "C17") (pin "2") (pinfunction "2_2") (pintype "passive"))
      (node (ref "J3") (pin "18") (pinfunction "18_18") (pintype "bidirectional"))
    )
    (net (code "26") (name "Net-(C19-Pad2)") (class "Default")
      (node (ref "C19") (pin "2") (pinfunction "2_2") (pintype "passive"))
      (node (ref "J3") (pin "4") (pinfunction "4_4") (pintype "bidirectional"))
    )
    (net (code "27") (name "Net-(C20-Pad2)") (class "Default")
      (node (ref "C20") (pin "2") (pinfunction "2_2") (pintype "passive"))
      (node (ref "J3") (pin "5") (pinfunction "5_5") (pintype "bidirectional"))
    )
    (net (code "28") (name "Net-(D2-CATHODE)") (class "Default")
      (node (ref "C4") (pin "1") (pinfunction "1_1") (pintype "passive"))
      (node (ref "D2") (pin "1") (pinfunction "CATHODE_1") (pintype "bidirectional"))
      (node (ref "IC1") (pin "1") (pinfunction "VIN_1") (pintype "bidirectional"))
      (node (ref "IC1") (pin "3") (pinfunction "CE_3") (pintype "bidirectional"))
      (node (ref "Q1") (pin "2") (pinfunction "S_2") (pintype "bidirectional"))
    )
    (net (code "29") (name "Net-(D3-K)") (class "Default")
      (node (ref "C9") (pin "1") (pinfunction "1_1") (pintype "passive"))
      (node (ref "D3") (pin "1") (pinfunction "K_1") (pintype "bidirectional"))
      (node (ref "D4") (pin "2") (pinfunction "A_2") (pintype "bidirectional"))
    )
    (net (code "30") (name "Net-(D6-CATHODE)") (class "Default")
      (node (ref "D6") (pin "1") (pinfunction "CATHODE_1") (pintype "bidirectional"))
      (node (ref "R18") (pin "1") (pinfunction "1_1") (pintype "passive"))
    )
    (net (code "31") (name "Net-(IC2-CT)") (class "Default")
      (node (ref "C23") (pin "1") (pinfunction "1_1") (pintype "passive"))
      (node (ref "IC2") (pin "5") (pinfunction "CT_5") (pintype "bidirectional"))
    )
    (net (code "32") (name "Net-(J1-PadA5)") (class "Default")
      (node (ref "J1") (pin "A5") (pinfunction "A5_A5") (pintype "bidirectional"))
      (node (ref "R2") (pin "2") (pinfunction "2_2") (pintype "passive"))
    )
    (net (code "33") (name "Net-(J1-PadB5)") (class "Default")
      (node (ref "J1") (pin "B5") (pinfunction "B5_B5") (pintype "bidirectional"))
      (node (ref "R3") (pin "1") (pinfunction "1_1") (pintype "passive"))
    )
    (net (code "34") (name "Net-(LED1-PadC)") (class "Default")
      (node (ref "LED1") (pin "C") (pinfunction "C_C") (pintype "passive"))
      (node (ref "R6") (pin "1") (pinfunction "1_1") (pintype "passive"))
    )
    (net (code "35") (name "Net-(U2-PROG)") (class "Default")
      (node (ref "R7") (pin "2") (pinfunction "2_2") (pintype "passive"))
      (node (ref "U2") (pin "5") (pinfunction "PROG_5") (pintype "input"))
    )
    (net (code "36") (name "Net-(U2-STAT)") (class "Default")
      (node (ref "R6") (pin "2") (pinfunction "2_2") (pintype "passive"))
      (node (ref "U2") (pin "1") (pinfunction "STAT_1") (pintype "output"))
    )
    (net (code "37") (name "PREVGH") (class "Default")
      (node (ref "C14") (pin "2") (pinfunction "2_2") (pintype "passive"))
      (node (ref "D5") (pin "1") (pinfunction "K_1") (pintype "bidirectional"))
      (node (ref "J3") (pin "21") (pinfunction "21_21") (pintype "bidirectional"))
    )
    (net (code "38") (name "PREVGL") (class "Default")
      (node (ref "C12") (pin "2") (pinfunction "2_2") (pintype "passive"))
      (node (ref "D3") (pin "2") (pinfunction "A_2") (pintype "bidirectional"))
      (node (ref "J3") (pin "23") (pinfunction "23_23") (pintype "bidirectional"))
    )
    (net (code "39") (name "RESE") (class "Default")
      (node (ref "J3") (pin "3") (pinfunction "3_3") (pintype "bidirectional"))
      (node (ref "Q2") (pin "2") (pinfunction "S_2") (pintype "bidirectional"))
      (node (ref "R9") (pin "2") (pinfunction "2_2") (pintype "passive"))
    )
    (net (code "40") (name "RESE'") (class "Default")
      (node (ref "R10") (pin "2") (pinfunction "2_2") (pintype "passive"))
      (node (ref "R9") (pin "1") (pinfunction "1_1") (pintype "passive"))
      (node (ref "SJ1") (pin "2") (pinfunction "2_2") (pintype "passive"))
    )
    (net (code "41") (name "RESET") (class "Default")
      (node (ref "C24") (pin "1") (pinfunction "1_1") (pintype "passive"))
      (node (ref "IC2") (pin "1") (pinfunction "VOUT_1") (pintype "bidirectional"))
      (node (ref "R15") (pin "1") (pinfunction "1_1") (pintype "passive"))
      (node (ref "U$1") (pin "3") (pinfunction "3_3") (pintype "passive"))
      (node (ref "U$1") (pin "4") (pinfunction "4_4") (pintype "passive"))
      (node (ref "U1") (pin "3") (pinfunction "EN_3") (pintype "input"))
    )
    (net (code "42") (name "RTC_RST") (class "Default")
      (node (ref "U1") (pin "16") (pinfunction "IO18_16") (pintype "bidirectional"))
      (node (ref "U5") (pin "4") (pinfunction "~{RST}_4") (pintype "input"))
    )
    (net (code "43") (name "RX") (class "Default")
      (node (ref "TP2") (pin "TP") (pinfunction "TP_TP") (pintype "input"))
      (node (ref "U1") (pin "24") (pinfunction "RXD0/GPIO17_24") (pintype "bidirectional"))
    )
    (net (code "44") (name "SCK") (class "Default")
      (node (ref "D9") (pin "1") (pinfunction "1_1") (pintype "passive"))
      (node (ref "J2") (pin "P5") (pinfunction "CLK_P5") (pintype "bidirectional"))
      (node (ref "J3") (pin "13") (pinfunction "13_13") (pintype "bidirectional"))
      (node (ref "R23") (pin "1") (pinfunction "1_1") (pintype "passive"))
      (node (ref "TP11") (pin "TP") (pinfunction "TP_TP") (pintype "input"))
      (node (ref "U1") (pin "6") (pinfunction "IO6_6") (pintype "bidirectional"))
      (node (ref "U6") (pin "6") (pinfunction "CLK_6") (pintype "input"))
    )
    (net (code "45") (name "SCL") (class "Default")
      (node (ref "J4") (pin "4") (pinfunction "4_4") (pintype "passive"))
      (node (ref "R13") (pin "1") (pinfunction "1_1") (pintype "passive"))
      (node (ref "U1") (pin "20") (pinfunction "IO22_20") (pintype "bidirectional"))
      (node (ref "U3") (pin "4") (pinfunction "SCK_4") (pintype "input"))
      (node (ref "U4") (pin "7") (pinfunction "SCL_7") (pintype "input"))
      (node (ref "U5") (pin "16") (pinfunction "SCL_16") (pintype "input"))
    )
    (net (code "46") (name "SDA") (class "Default")
      (node (ref "J4") (pin "3") (pinfunction "3_3") (pintype "passive"))
      (node (ref "R14") (pin "1") (pinfunction "1_1") (pintype "passive"))
      (node (ref "U1") (pin "19") (pinfunction "IO21_19") (pintype "bidirectional"))
      (node (ref "U3") (pin "3") (pinfunction "SDI_3") (pintype "bidirectional"))
      (node (ref "U4") (pin "8") (pinfunction "SDA_8") (pintype "bidirectional"))
      (node (ref "U5") (pin "15") (pinfunction "SDA_15") (pintype "bidirectional"))
    )
    (net (code "47") (name "SRC") (class "Default")
      (node (ref "C9") (pin "2") (pinfunction "2_2") (pintype "passive"))
      (node (ref "D5") (pin "2") (pinfunction "A_2") (pintype "bidirectional"))
      (node (ref "L1") (pin "1") (pinfunction "1_1") (pintype "passive"))
      (node (ref "Q2") (pin "3") (pinfunction "D_3") (pintype "bidirectional"))
    )
    (net (code "48") (name "SS_SD") (class "Default")
      (node (ref "D12") (pin "1") (pinfunction "1_1") (pintype "passive"))
      (node (ref "J2") (pin "P2") (pinfunction "CD/DAT3_P2") (pintype "bidirectional"))
      (node (ref "R26") (pin "1") (pinfunction "1_1") (pintype "passive"))
      (node (ref "U1") (pin "4") (pinfunction "IO4_4") (pintype "bidirectional"))
    )
    (net (code "49") (name "TX") (class "Default")
      (node (ref "TP1") (pin "TP") (pinfunction "TP_TP") (pintype "input"))
      (node (ref "U1") (pin "25") (pinfunction "TXD0/GPIO16_25") (pintype "bidirectional"))
    )
    (net (code "50") (name "USB_D+") (class "Default")
      (node (ref "D1") (pin "3") (pinfunction "I/O2_1_3") (pintype "bidirectional"))
      (node (ref "U1") (pin "14") (pinfunction "IO13_14") (pintype "bidirectional"))
    )
    (net (code "51") (name "USB_D-") (class "Default")
      (node (ref "D1") (pin "1") (pinfunction "I/O1_1_1") (pintype "bidirectional"))
      (node (ref "U1") (pin "13") (pinfunction "IO12_13") (pintype "bidirectional"))
    )
    (net (code "52") (name "VBAT") (class "Default")
      (node (ref "C8") (pin "1") (pinfunction "1_1") (pintype "passive"))
      (node (ref "Q1") (pin "3") (pinfunction "D_3") (pintype "bidirectional"))
      (node (ref "TP3") (pin "TP") (pinfunction "TP_TP") (pintype "input"))
      (node (ref "U2") (pin "3") (pinfunction "VBAT_3") (pintype "power_in"))
      (node (ref "U4") (pin "2") (pinfunction "CELL_2") (pintype "power_in"))
      (node (ref "U4") (pin "3") (pinfunction "VDD_3") (pintype "power_in"))
    )
    (net (code "53") (name "VBUS") (class "Default")
      (node (ref "C7") (pin "1") (pinfunction "1_1") (pintype "passive"))
      (node (ref "D1") (pin "5") (pinfunction "VBUS_5") (pintype "bidirectional"))
      (node (ref "D2") (pin "2") (pinfunction "ANODE_2") (pintype "bidirectional"))
      (node (ref "LED1") (pin "A") (pinfunction "A_A") (pintype "passive"))
      (node (ref "Q1") (pin "1") (pinfunction "G_1") (pintype "bidirectional"))
      (node (ref "R1") (pin "2") (pinfunction "2_2") (pintype "passive"))
      (node (ref "R4") (pin "2") (pinfunction "2_2") (pintype "passive"))
      (node (ref "TP17") (pin "TP") (pinfunction "TP_TP") (pintype "input"))
      (node (ref "U2") (pin "4") (pinfunction "VIN_4") (pintype "power_in"))
    )
    (net (code "54") (name "VRTC") (class "Default")
      (node (ref "C27") (pin "1") (pinfunction "1_1") (pintype "passive"))
      (node (ref "C28") (pin "2") (pinfunction "2_2") (pintype "passive"))
      (node (ref "R18") (pin "2") (pinfunction "2_2") (pintype "passive"))
      (node (ref "U5") (pin "14") (pinfunction "VBAT_14") (pintype "power_in"))
    )
    (net (code "55") (name "VUSB") (class "Default")
      (node (ref "J1") (pin "A4") (pinfunction "A4_A4") (pintype "bidirectional"))
      (node (ref "J1") (pin "A9") (pinfunction "A9_A9") (pintype "bidirectional"))
      (node (ref "J1") (pin "B4") (pinfunction "B4_B4") (pintype "bidirectional"))
      (node (ref "J1") (pin "B9") (pinfunction "B9_B9") (pintype "bidirectional"))
      (node (ref "R1") (pin "1") (pinfunction "1_1") (pintype "passive"))
    )
    (net (code "56") (name "unconnected-(IC1-NC-Pad4)") (class "Default")
      (node (ref "IC1") (pin "4") (pinfunction "NC_4") (pintype "no_connect"))
    )
    (net (code "57") (name "unconnected-(IC2-NC-Pad4)") (class "Default")
      (node (ref "IC2") (pin "4") (pinfunction "NC_4") (pintype "no_connect"))
    )
    (net (code "58") (name "unconnected-(J1-PadA8)") (class "Default")
      (node (ref "J1") (pin "A8") (pinfunction "A8_A8") (pintype "bidirectional"))
    )
    (net (code "59") (name "unconnected-(J1-PadB8)") (class "Default")
      (node (ref "J1") (pin "B8") (pinfunction "B8_B8") (pintype "bidirectional"))
    )
    (net (code "60") (name "unconnected-(J2-DAT1-PadP8)") (class "Default")
      (node (ref "J2") (pin "P8") (pinfunction "DAT1_P8") (pintype "bidirectional"))
    )
    (net (code "61") (name "unconnected-(J2-DAT2-PadP1)") (class "Default")
      (node (ref "J2") (pin "P1") (pinfunction "DAT2_P1") (pintype "bidirectional"))
    )
    (net (code "62") (name "unconnected-(J2-DETECTION_1-PadS1)") (class "Default")
      (node (ref "J2") (pin "S1") (pinfunction "DETECTION_1_S1") (pintype "bidirectional"))
    )
    (net (code "63") (name "unconnected-(J2-DETECTION_2-PadS2)") (class "Default")
      (node (ref "J2") (pin "S2") (pinfunction "DETECTION_2_S2") (pintype "bidirectional"))
    )
    (net (code "64") (name "unconnected-(J3-Pad1)") (class "Default")
      (node (ref "J3") (pin "1") (pinfunction "1_1") (pintype "bidirectional"))
    )
    (net (code "65") (name "unconnected-(J3-Pad6)") (class "Default")
      (node (ref "J3") (pin "6") (pinfunction "6_6") (pintype "bidirectional"))
    )
    (net (code "66") (name "unconnected-(J3-Pad7)") (class "Default")
      (node (ref "J3") (pin "7") (pinfunction "7_7") (pintype "bidirectional"))
    )
    (net (code "67") (name "unconnected-(U1-NC-Pad22)") (class "Default")
      (node (ref "U1") (pin "22") (pinfunction "NC_22") (pintype "no_connect"))
    )
    (net (code "68") (name "unconnected-(U4-~{ALERT}-Pad5)") (class "Default")
      (node (ref "U4") (pin "5") (pinfunction "~{ALERT}_5") (pintype "output"))
    )
  )
)
